# CSI2-KRIA-KV260_Rev01-2.net
KiCad netlist of a schematic drawn in Altium Designer
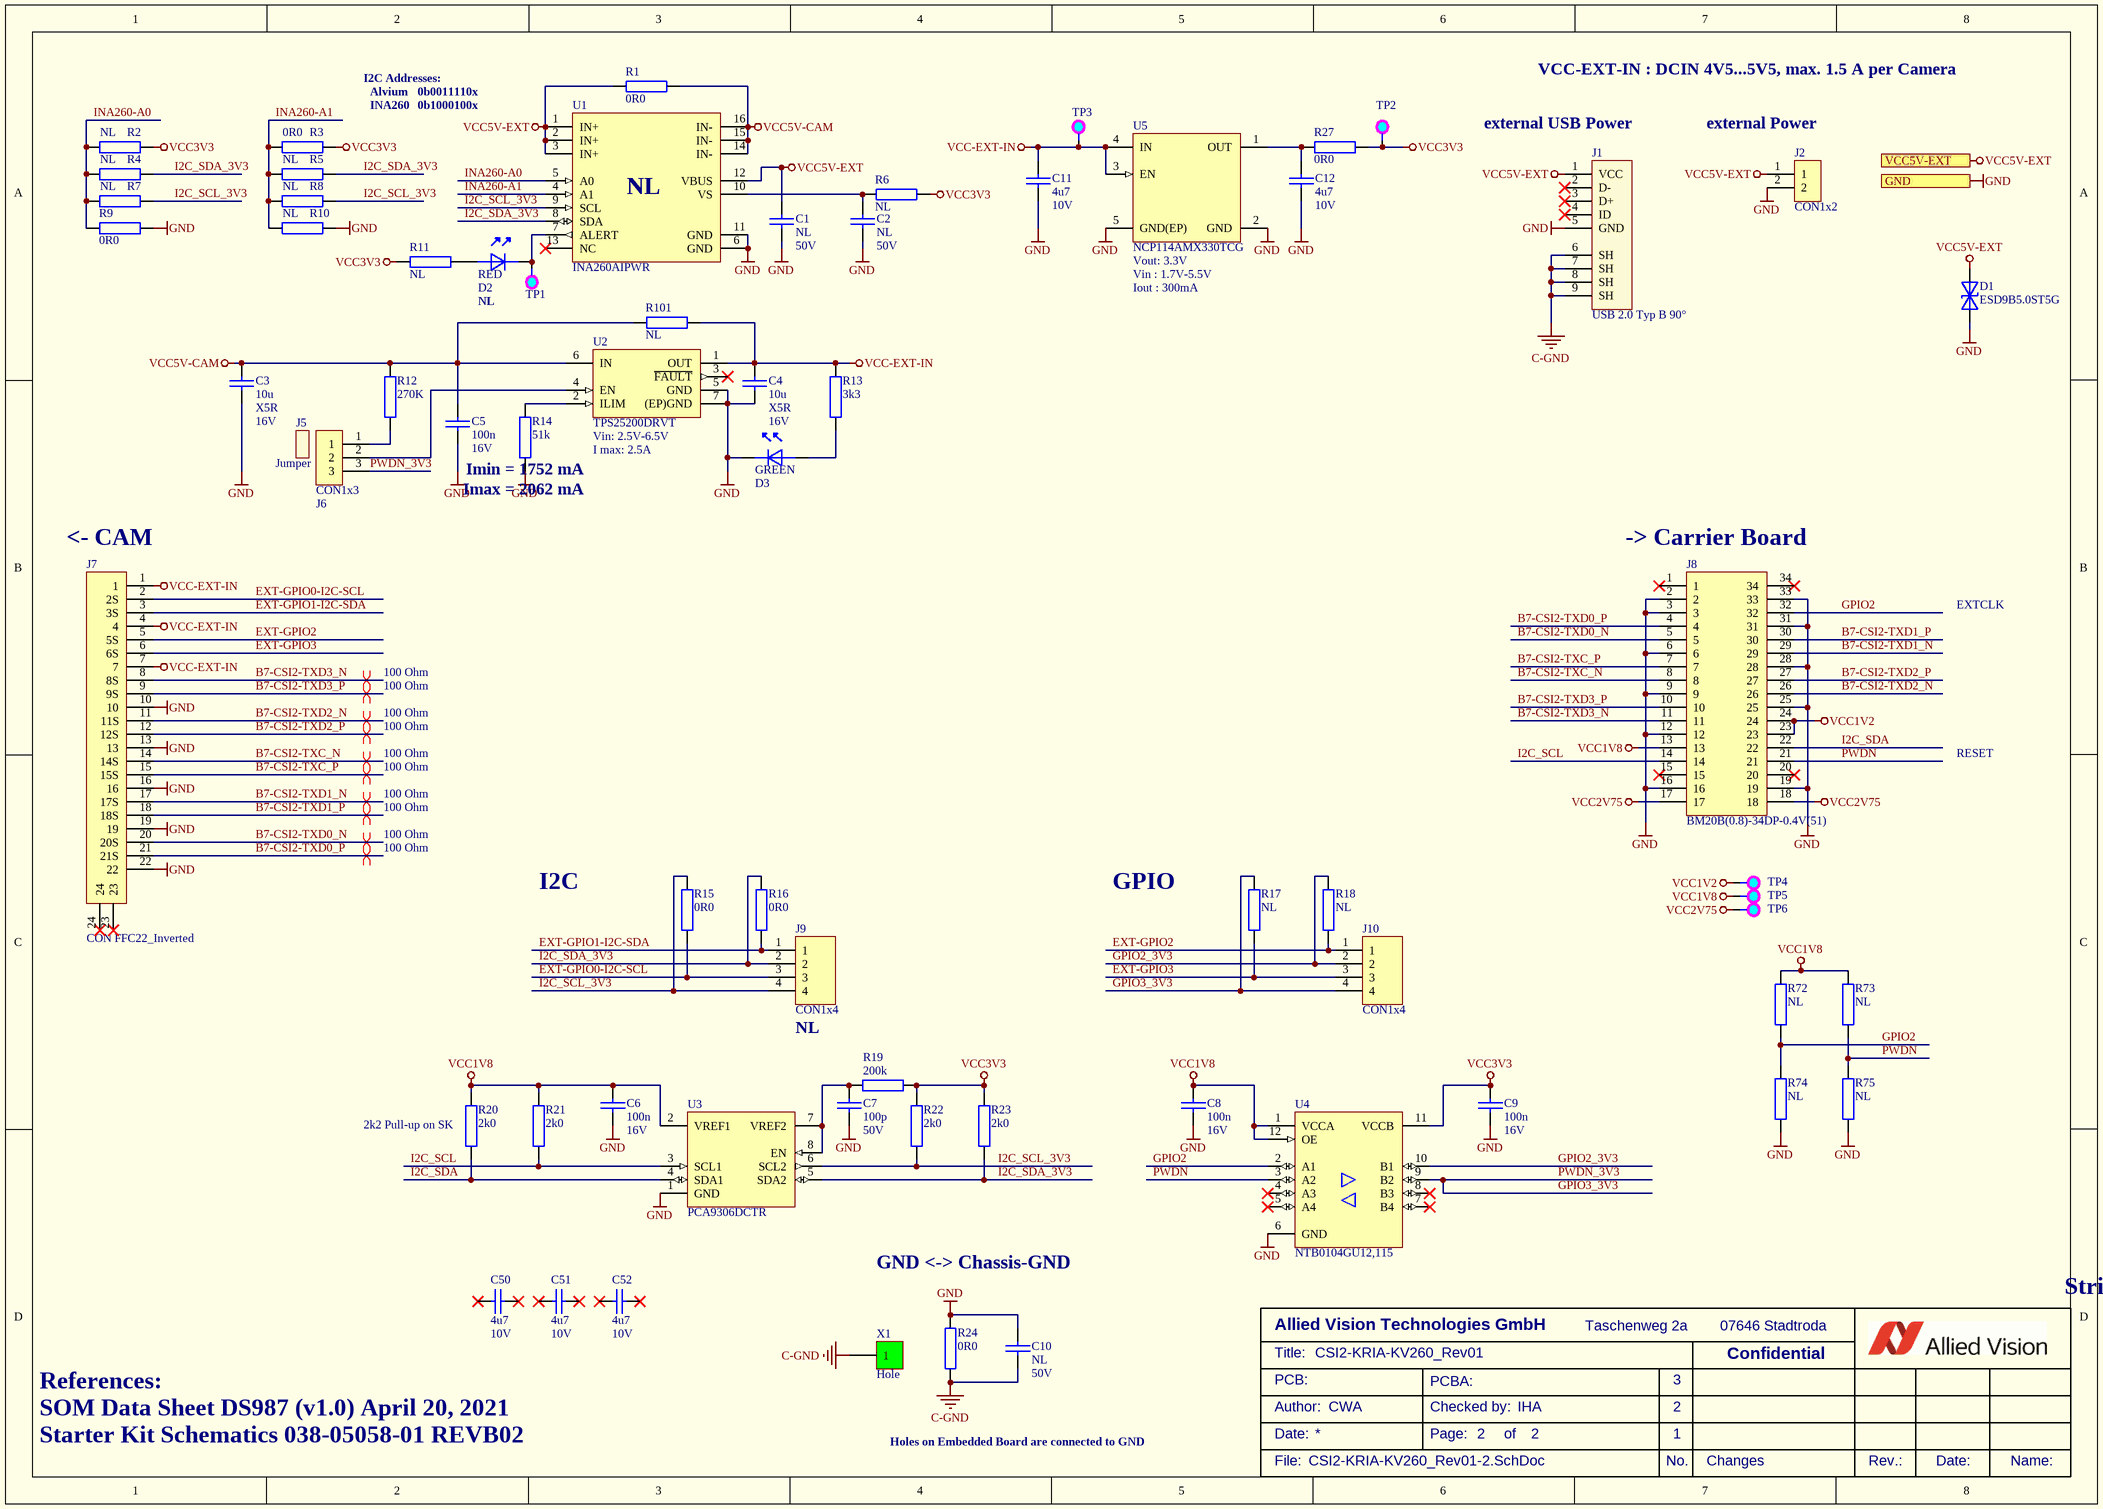
[diagram p0: CSI2-KRIA-KV260_Rev01-2.SchDoc]

(export (version "E")
  (design (tool "Eeschema 10.0.6"))
  (components
    (comp (ref "C1")
      (value "NL")
      (footprint "C-0402_0.55")
      (description "Capacitor Ceramic SMD/0402/50V/X7R/10%")
      (fields
        (field (name "MANUFACTURER") "several")
        (field (name "TOLERANCE") "10%")
        (field (name "VOLTAGE") "50V")
      )
      (libsource (lib "AVT_KHK_Lib") (part "C X 0402"))
    )
    (comp (ref "C2")
      (value "NL")
      (footprint "C-0402_0.55")
      (description "Capacitor Ceramic SMD/0402/50V/X7R/10%")
      (fields
        (field (name "MANUFACTURER") "several")
        (field (name "TOLERANCE") "10%")
        (field (name "VOLTAGE") "50V")
      )
      (libsource (lib "AVT_KHK_Lib") (part "C X 0402"))
    )
    (comp (ref "C3")
      (value "10u")
      (footprint "C-0805_1.4")
      (description "Capacitor Ceramic SMD/0805/16V/X5R/10%")
      (fields
        (field (name "KHK PART NUMBER") "K8340151")
        (field (name "MANUFACTURER") "several")
        (field (name "DIELECTRIC") "X5R")
        (field (name "VOLTAGE") "16V")
      )
      (libsource (lib "Passive") (part "C 10U 16V X5R 0805"))
    )
    (comp (ref "C4")
      (value "10u")
      (footprint "C-0805_1.4")
      (description "Capacitor Ceramic SMD/0805/16V/X5R/10%")
      (fields
        (field (name "KHK PART NUMBER") "K8340151")
        (field (name "MANUFACTURER") "several")
        (field (name "DIELECTRIC") "X5R")
        (field (name "VOLTAGE") "16V")
      )
      (libsource (lib "Passive") (part "C 10U 16V X5R 0805"))
    )
    (comp (ref "C5")
      (value "100n")
      (footprint "C-0402_0.55")
      (description "Capacitor Ceramic SMD/0402/16V/X7R/10%")
      (fields
        (field (name "KHK PART NUMBER") "K8340114")
        (field (name "MANUFACTURER") "several")
        (field (name "VOLTAGE") "16V")
      )
      (libsource (lib "Passive") (part "C 100N 10% 16V X7R 402"))
    )
    (comp (ref "C6")
      (value "100n")
      (footprint "C-0402_0.55")
      (description "Capacitor Ceramic SMD/0402/16V/X7R/10%")
      (fields
        (field (name "KHK PART NUMBER") "K8340114")
        (field (name "MANUFACTURER") "several")
        (field (name "VOLTAGE") "16V")
      )
      (libsource (lib "Passive") (part "C 100N 10% 16V X7R 402"))
    )
    (comp (ref "C7")
      (value "100p")
      (footprint "C-0402_0.55")
      (description "Capacitor Ceramic SMD/0402/50V/X7R/10%")
      (fields
        (field (name "KHK PART NUMBER") "K8340145")
        (field (name "MANUFACTURER") "several")
        (field (name "VOLTAGE") "50V")
      )
      (libsource (lib "Passive") (part "C 100P 50V X7R 0402"))
    )
    (comp (ref "C8")
      (value "100n")
      (footprint "C-0402_0.55")
      (description "Capacitor Ceramic SMD/0402/16V/X7R/10%")
      (fields
        (field (name "KHK PART NUMBER") "K8340114")
        (field (name "MANUFACTURER") "several")
        (field (name "VOLTAGE") "16V")
      )
      (libsource (lib "Passive") (part "C 100N 10% 16V X7R 402"))
    )
    (comp (ref "C9")
      (value "100n")
      (footprint "C-0402_0.55")
      (description "Capacitor Ceramic SMD/0402/16V/X7R/10%")
      (fields
        (field (name "KHK PART NUMBER") "K8340114")
        (field (name "MANUFACTURER") "several")
        (field (name "VOLTAGE") "16V")
      )
      (libsource (lib "Passive") (part "C 100N 10% 16V X7R 402"))
    )
    (comp (ref "C10")
      (value "NL")
      (footprint "C-0603_1.0")
      (description "Capacitor Ceramic SMD/0603/50V/X7R/10%")
      (fields
        (field (name "MANUFACTURER") "several")
        (field (name "TOLERANCE") "10%")
        (field (name "VOLTAGE") "50V")
      )
      (libsource (lib "AVT_KHK_Lib") (part "C X 0603"))
    )
    (comp (ref "C11")
      (value "4u7")
      (footprint "C-0603_1.0")
      (description "Capacitor Ceramic SMD/0603/10V/X5R/10%")
      (fields
        (field (name "KHK PART NUMBER") "1431")
        (field (name "MANUFACTURER") "several")
        (field (name "VOLTAGE") "10V")
      )
      (libsource (lib "Passive") (part "C 4U7 10V X5R 0603"))
    )
    (comp (ref "C12")
      (value "4u7")
      (footprint "C-0603_1.0")
      (description "Capacitor Ceramic SMD/0603/10V/X5R/10%")
      (fields
        (field (name "KHK PART NUMBER") "1431")
        (field (name "MANUFACTURER") "several")
        (field (name "VOLTAGE") "10V")
      )
      (libsource (lib "Passive") (part "C 4U7 10V X5R 0603"))
    )
    (comp (ref "C50")
      (value "4u7")
      (footprint "C-0603_1.0")
      (description "Capacitor Ceramic SMD/0603/10V/X5R/10%")
      (fields
        (field (name "KHK PART NUMBER") "1431")
        (field (name "MANUFACTURER") "several")
        (field (name "VOLTAGE") "10V")
      )
      (libsource (lib "Passive") (part "C 4U7 10V X5R 0603"))
    )
    (comp (ref "C51")
      (value "4u7")
      (footprint "C-0603_1.0")
      (description "Capacitor Ceramic SMD/0603/10V/X5R/10%")
      (fields
        (field (name "KHK PART NUMBER") "1431")
        (field (name "MANUFACTURER") "several")
        (field (name "VOLTAGE") "10V")
      )
      (libsource (lib "Passive") (part "C 4U7 10V X5R 0603"))
    )
    (comp (ref "C52")
      (value "4u7")
      (footprint "C-0603_1.0")
      (description "Capacitor Ceramic SMD/0603/10V/X5R/10%")
      (fields
        (field (name "KHK PART NUMBER") "1431")
        (field (name "MANUFACTURER") "several")
        (field (name "VOLTAGE") "10V")
      )
      (libsource (lib "Passive") (part "C 4U7 10V X5R 0603"))
    )
    (comp (ref "D1")
      (value "ESD9B5.0ST5G")
      (footprint "D-SOD923")
      (description "DIODE TVS; 400W; 5.8-7.8V; BIDIRECT")
      (fields (field (name "KHK PART NUMBER") "7250") (field (name "MANUFACTURER") "ON Semiconductor"))
      (libsource (lib "Bipolar") (part "D ESD9B5.0ST5G"))
    )
    (comp (ref "D2")
      (value "RED")
      (footprint "D-0603-LED")
      (description "Chip LED red 250mcd")
      (fields (field (name "KHK PART NUMBER") "8145") (field (name "MANUFACTURER") "Würth"))
      (libsource (lib "Bipolar") (part "D LED 0603 red"))
    )
    (comp (ref "D3")
      (value "GREEN")
      (footprint "D-0603-LED")
      (description "Chip LED green 430mcd")
      (fields (field (name "KHK PART NUMBER") "8172") (field (name "MANUFACTURER") "Würth"))
      (libsource (lib "Bipolar") (part "D LED 0603 green"))
    )
    (comp (ref "J1")
      (value "USB 2.0 Typ B 90°")
      (footprint "J-629105150521")
      (description "Micro USB 2.0 Typ B 90°")
      (fields (field (name "KHK PART NUMBER") "14360") (field (name "MANUFACTURER") "WE"))
      (libsource (lib "Connector") (part "CON USB 2.0 Typ B 90°"))
    )
    (comp (ref "J2")
      (value "CON1x2")
      (footprint "CON 1x2 RM2.54")
      (fields (field (name "MANUFACTURER") "several") (field (name "KHK PART NUMBER") "15337"))
      (libsource (lib "Connector") (part "CON 1x2 2.54 several"))
    )
    (comp (ref "J5")
      (value "Jumper")
      (footprint "J-JUMPER-2.54")
      (description "CON/JUMPER/STC02SYAN; 2-pin; 2.54mm; 3A; FEMALE; VERTICAL; BLACK")
      (fields (field (name "KHK PART NUMBER") "13444") (field (name "MANUFACTURER") "several"))
      (libsource (lib "Connector") (part "CON Jumper 2.54mm"))
    )
    (comp (ref "J6")
      (value "CON1x3")
      (footprint "CON 1x3 RM2.54")
      (fields (field (name "MANUFACTURER") "several") (field (name "KHK PART NUMBER") "15338"))
      (libsource (lib "Connector") (part "CON 1x3 2.54 several"))
    )
    (comp (ref "J7")
      (value "CON FFC22_Inverted")
      (footprint "J-FH55-22S-0.5SH - Inverted Pins")
      (description "FFC Connector 0.5mm shielded")
      (fields
        (field (name "KHK PART NUMBER") "10357")
        (field (name "MANUFACTURER PART NUMBER") "FH55-22S-0.5SH")
      )
      (libsource (lib "Connector") (part "CON FFC22_FH55-22S-0.5SH_Inverted"))
    )
    (comp (ref "J8")
      (value "BM20B(0.8)-34DP-0.4V(51)")
      (footprint "J-BM20B(0.8)-34DP")
      (description "CON/B2B/BM20B;34-pin;0.4;SMT;HEADER;VERTICAL")
      (fields (field (name "MANUFACTURER") "HiRose") (field (name "KHK PART NUMBER") "18690"))
      (libsource (lib "AVT_KHK_Lib") (part "CON BM20B(0.8)-34DP"))
    )
    (comp (ref "J9")
      (value "CON1x4")
      (footprint "CON 1x4 RM2.54")
      (fields (field (name "MANUFACTURER") "several") (field (name "KHK PART NUMBER") "15343"))
      (libsource (lib "Connector") (part "CON 1x4 2.54 several"))
    )
    (comp (ref "J10")
      (value "CON1x4")
      (footprint "CON 1x4 RM2.54")
      (fields (field (name "MANUFACTURER") "several") (field (name "KHK PART NUMBER") "15343"))
      (libsource (lib "Connector") (part "CON 1x4 2.54 several"))
    )
    (comp (ref "R1")
      (value "0R0")
      (footprint "R-0603_0.6")
      (description "Standard Resistor SMD/0603/1%/100mW/TK200")
      (fields (field (name "KHK PART NUMBER") "K8250041") (field (name "MANUFACTURER") "several"))
      (libsource (lib "AVT_KHK_Lib") (part "R 0R0 1% 0603"))
    )
    (comp (ref "R2")
      (value "NL")
      (footprint "R-0603_0.6")
      (description "Standard Resistor SMD/0603/1%/100mW/TK200")
      (fields (field (name "TOLERANCE") "1%"))
      (libsource (lib "AVT_KHK_Lib") (part "R X 0603"))
    )
    (comp (ref "R3")
      (value "0R0")
      (footprint "R-0603_0.6")
      (description "Standard Resistor SMD/0603/1%/100mW/TK200")
      (fields (field (name "KHK PART NUMBER") "K8250041") (field (name "MANUFACTURER") "several"))
      (libsource (lib "Passive") (part "R 0R0 1% 0603"))
    )
    (comp (ref "R4")
      (value "NL")
      (footprint "R-0603_0.6")
      (description "Standard Resistor SMD/0603/1%/100mW/TK200")
      (fields (field (name "TOLERANCE") "1%"))
      (libsource (lib "AVT_KHK_Lib") (part "R X 0603"))
    )
    (comp (ref "R5")
      (value "NL")
      (footprint "R-0603_0.6")
      (description "Standard Resistor SMD/0603/1%/100mW/TK200")
      (fields (field (name "TOLERANCE") "1%"))
      (libsource (lib "AVT_KHK_Lib") (part "R X 0603"))
    )
    (comp (ref "R6")
      (value "NL")
      (footprint "R-0603_0.6")
      (description "Standard Resistor SMD/0603/1%/100mW/TK200")
      (fields (field (name "TOLERANCE") "1%"))
      (libsource (lib "AVT_KHK_Lib") (part "R X 0603"))
    )
    (comp (ref "R7")
      (value "NL")
      (footprint "R-0603_0.6")
      (description "Standard Resistor SMD/0603/1%/100mW/TK200")
      (fields (field (name "TOLERANCE") "1%"))
      (libsource (lib "AVT_KHK_Lib") (part "R X 0603"))
    )
    (comp (ref "R8")
      (value "NL")
      (footprint "R-0603_0.6")
      (description "Standard Resistor SMD/0603/1%/100mW/TK200")
      (fields (field (name "TOLERANCE") "1%"))
      (libsource (lib "AVT_KHK_Lib") (part "R X 0603"))
    )
    (comp (ref "R9")
      (value "0R0")
      (footprint "R-0603_0.6")
      (description "Standard Resistor SMD/0603/1%/100mW/TK200")
      (fields (field (name "KHK PART NUMBER") "K8250041") (field (name "MANUFACTURER") "several"))
      (libsource (lib "Passive") (part "R 0R0 1% 0603"))
    )
    (comp (ref "R10")
      (value "NL")
      (footprint "R-0603_0.6")
      (description "Standard Resistor SMD/0603/1%/100mW/TK200")
      (fields (field (name "TOLERANCE") "1%"))
      (libsource (lib "AVT_KHK_Lib") (part "R X 0603"))
    )
    (comp (ref "R11")
      (value "NL")
      (footprint "R-0402_0.4")
      (description "Standard Resistor SMD/0402/1%/63mW/TK200")
      (fields (field (name "TOLERANCE") "1%"))
      (libsource (lib "AVT_KHK_Lib") (part "R X 0402"))
    )
    (comp (ref "R12")
      (value "270K")
      (footprint "R-0402_0.4")
      (description "Standard Resistor SMD/0402/1%/63mW/TK100")
      (fields (field (name "KHK PART NUMBER") "3875") (field (name "MANUFACTURER") "several"))
      (libsource (lib "Passive") (part "R 270K 1% 0402"))
    )
    (comp (ref "R13")
      (value "3k3")
      (footprint "R-0402_0.4")
      (description "Standard Resistor SMD/0402/1%/63mW/TK100")
      (fields (field (name "KHK PART NUMBER") "K8250347") (field (name "MANUFACTURER") "several"))
      (libsource (lib "Passive") (part "R 3k3 1% 0402"))
    )
    (comp (ref "R14")
      (value "51k")
      (footprint "R-0402_0.4")
      (description "Standard Resistor SMD/0402/1%/63mW/TK100")
      (fields (field (name "KHK PART NUMBER") "K8250273") (field (name "MANUFACTURER") "several"))
      (libsource (lib "Passive") (part "R 51K 1% 0402"))
    )
    (comp (ref "R15")
      (value "0R0")
      (footprint "R-0603_0.6")
      (description "Standard Resistor SMD/0603/1%/100mW/TK200")
      (fields (field (name "KHK PART NUMBER") "K8250041") (field (name "MANUFACTURER") "several"))
      (libsource (lib "Passive") (part "R 0R0 1% 0603"))
    )
    (comp (ref "R16")
      (value "0R0")
      (footprint "R-0603_0.6")
      (description "Standard Resistor SMD/0603/1%/100mW/TK200")
      (fields (field (name "KHK PART NUMBER") "K8250041") (field (name "MANUFACTURER") "several"))
      (libsource (lib "Passive") (part "R 0R0 1% 0603"))
    )
    (comp (ref "R17")
      (value "NL")
      (footprint "R-0603_0.6")
      (description "Standard Resistor SMD/0603/1%/100mW/TK200")
      (fields (field (name "TOLERANCE") "1%"))
      (libsource (lib "AVT_KHK_Lib") (part "R X 0603"))
    )
    (comp (ref "R18")
      (value "NL")
      (footprint "R-0603_0.6")
      (description "Standard Resistor SMD/0603/1%/100mW/TK200")
      (fields (field (name "TOLERANCE") "1%"))
      (libsource (lib "AVT_KHK_Lib") (part "R X 0603"))
    )
    (comp (ref "R19")
      (value "200k")
      (footprint "R-0402_0.4")
      (description "Standard Resistor SMD/0402/1%/63mW/TK100")
      (fields (field (name "KHK PART NUMBER") "K8250280") (field (name "MANUFACTURER") "several"))
      (libsource (lib "Passive") (part "R 200K 1% 0402"))
    )
    (comp (ref "R20")
      (value "2k0")
      (footprint "R-0402_0.4")
      (description "Standard Resistor SMD/0402/1%/63mW/TK100")
      (fields (field (name "KHK PART NUMBER") "K8250311") (field (name "MANUFACTURER") "several"))
      (libsource (lib "Passive") (part "R 2k0 1% 0402"))
    )
    (comp (ref "R21")
      (value "2k0")
      (footprint "R-0402_0.4")
      (description "Standard Resistor SMD/0402/1%/63mW/TK100")
      (fields (field (name "KHK PART NUMBER") "K8250311") (field (name "MANUFACTURER") "several"))
      (libsource (lib "Passive") (part "R 2k0 1% 0402"))
    )
    (comp (ref "R22")
      (value "2k0")
      (footprint "R-0402_0.4")
      (description "Standard Resistor SMD/0402/1%/63mW/TK100")
      (fields (field (name "KHK PART NUMBER") "K8250311") (field (name "MANUFACTURER") "several"))
      (libsource (lib "Passive") (part "R 2k0 1% 0402"))
    )
    (comp (ref "R23")
      (value "2k0")
      (footprint "R-0402_0.4")
      (description "Standard Resistor SMD/0402/1%/63mW/TK100")
      (fields (field (name "KHK PART NUMBER") "K8250311") (field (name "MANUFACTURER") "several"))
      (libsource (lib "Passive") (part "R 2k0 1% 0402"))
    )
    (comp (ref "R24")
      (value "0R0")
      (footprint "R-0603_0.6")
      (description "Standard Resistor SMD/0603/1%/100mW/TK200")
      (fields (field (name "KHK PART NUMBER") "K8250041") (field (name "MANUFACTURER") "several"))
      (libsource (lib "Passive") (part "R 0R0 1% 0603"))
    )
    (comp (ref "R27")
      (value "0R0")
      (footprint "R-0603_0.6")
      (description "Standard Resistor SMD/0603/1%/100mW/TK100")
      (fields (field (name "KHK PART NUMBER") "K8250041") (field (name "MANUFACTURER") "several"))
      (libsource (lib "Passive") (part "R 0R0 1% 0603"))
    )
    (comp (ref "R72")
      (value "NL")
      (footprint "R-0603_0.6")
      (description "Standard Resistor SMD/0603/1%/100mW/TK200")
      (fields (field (name "TOLERANCE") "1%"))
      (libsource (lib "AVT_KHK_Lib") (part "R X 0603"))
    )
    (comp (ref "R73")
      (value "NL")
      (footprint "R-0603_0.6")
      (description "Standard Resistor SMD/0603/1%/100mW/TK200")
      (fields (field (name "TOLERANCE") "1%"))
      (libsource (lib "AVT_KHK_Lib") (part "R X 0603"))
    )
    (comp (ref "R74")
      (value "NL")
      (footprint "R-0603_0.6")
      (description "Standard Resistor SMD/0603/1%/100mW/TK200")
      (fields (field (name "TOLERANCE") "1%"))
      (libsource (lib "AVT_KHK_Lib") (part "R X 0603"))
    )
    (comp (ref "R75")
      (value "NL")
      (footprint "R-0603_0.6")
      (description "Standard Resistor SMD/0603/1%/100mW/TK200")
      (fields (field (name "TOLERANCE") "1%"))
      (libsource (lib "AVT_KHK_Lib") (part "R X 0603"))
    )
    (comp (ref "R101")
      (value "NL")
      (footprint "R-0603_0.6")
      (description "Standard Resistor SMD/0603/1%/100mW/TK200")
      (fields (field (name "TOLERANCE") "1%"))
      (libsource (lib "AVT_KHK_Lib") (part "R X 0603"))
    )
    (comp (ref "TP1")
      (value "TP")
      (footprint "TP_16_10")
      (description "Testpoint: Pad=1,6mm; Hole=1,0mm")
      (libsource (lib "AVT_KHK_Lib") (part "TP_16_10"))
    )
    (comp (ref "TP2")
      (value "TP")
      (footprint "TP_16_10")
      (description "Testpoint: Pad=1,6mm; Hole=1,0mm")
      (libsource (lib "AVT_KHK_Lib") (part "TP_16_10"))
    )
    (comp (ref "TP3")
      (value "TP")
      (footprint "TP_16_10")
      (description "Testpoint: Pad=1,6mm; Hole=1,0mm")
      (libsource (lib "AVT_KHK_Lib") (part "TP_16_10"))
    )
    (comp (ref "TP4")
      (value "TP")
      (footprint "TP_16_10")
      (description "Testpoint: Pad=1,6mm; Hole=1,0mm")
      (libsource (lib "AVT_KHK_Lib") (part "TP_16_10"))
    )
    (comp (ref "TP5")
      (value "TP")
      (footprint "TP_16_10")
      (description "Testpoint: Pad=1,6mm; Hole=1,0mm")
      (libsource (lib "AVT_KHK_Lib") (part "TP_16_10"))
    )
    (comp (ref "TP6")
      (value "TP")
      (footprint "TP_16_10")
      (description "Testpoint: Pad=1,6mm; Hole=1,0mm")
      (libsource (lib "AVT_KHK_Lib") (part "TP_16_10"))
    )
    (comp (ref "U1")
      (value "INA260AIPWR")
      (footprint "IC-TSSOP16 6.4x5.1x1.2")
      (description "IC/PWR/CURR SHUNT MONITOR/2.7-5.5V;4.5mR/TSSOP16/5.0x4.4x1.2mm")
      (fields (field (name "KHK PART NUMBER") "16206") (field (name "MANUFACTURER") "TI"))
      (libsource (lib "Power") (part "IC INA260"))
    )
    (comp (ref "U2")
      (value "TPS25200DRVT")
      (footprint "IC-DFN06_2.0x2.0x0.8")
      (description "IC/PWR/LOADSW;2V5-6V5;2A5;0R099/6-WDFN/2x2x0.8mm")
      (fields
        (field (name "KHK PART NUMBER") "14277")
        (field (name "MANUFACTURER") "Texas Instruments")
        (field (name "VIN") "2.5V-6.5V")
        (field (name "I MAX") "2.5A")
      )
      (libsource (lib "Power") (part "IC  TPS25200DRVT"))
    )
    (comp (ref "U3")
      (value "PCA9306DCTR")
      (footprint "IC-TSSOP8_3.15x4.25x1.3")
      (description "IC/LOGIC/LEVELSHIFTER;I2C;AUTO-DIR;1V2-5V/SSOP-8/4.25x3.15x1.3mm")
      (fields (field (name "KHK PART NUMBER") "9555") (field (name "MANUFACTURER") "TI"))
      (libsource (lib "Logic") (part "IC PCA9306DCTR"))
    )
    (comp (ref "U4")
      (value "NTB0104GU12,115")
      (footprint "IC-XQFN12_1.7x2x0.5")
      (description "IC/LOGIC/Levelshifter;Auto-Dir;Bidirectional;Push-Pull;-40-+125°C/")
      (fields (field (name "MANUFACTURER") "NXP") (field (name "KHK PART NUMBER") "14383"))
      (libsource (lib "Logic") (part "IC NTB0104GU12,115"))
    )
    (comp (ref "U5")
      (value "NCP114AMX330TCG")
      (footprint "IC-XDFN4_1.0x1.0x0.6")
      (description "IC/PWR/LDO;1V7-5V5;3V3;0A3/XDFN4/1x1x0.6mm")
      (fields
        (field (name "KHK PART NUMBER") "20303")
        (field (name "MANUFACTURER") "ON Semi")
        (field (name "VOUT") "3.3V")
        (field (name "VIN") "Vin : 1.7V-5.5V")
        (field (name "IOUT") "Iout : 300mA")
      )
      (libsource (lib "AVT_KHK_Lib") (part "IC NCP114AMX330TCG"))
    )
    (comp (ref "X1")
      (value "Hole")
      (footprint "HOLE-3.4-6.0-DK")
      (description "HOLE 3.4-6-M3 Alternative")
      (libsource (lib "AVT_KHK_Lib") (part "PCB HOLE 3.4-6-DK"))
    )
  )
  (nets
    (net (code "1") (name "/B7-CSI2-TXC_N") (class "Default")
      (node (ref "J7") (pin "14") (pinfunction "14S_14") (pintype "passive"))
      (node (ref "J8") (pin "8") (pinfunction "8_8") (pintype "passive"))
    )
    (net (code "2") (name "/B7-CSI2-TXC_P") (class "Default")
      (node (ref "J7") (pin "15") (pinfunction "15S_15") (pintype "passive"))
      (node (ref "J8") (pin "7") (pinfunction "7_7") (pintype "passive"))
    )
    (net (code "3") (name "/B7-CSI2-TXD0_N") (class "Default")
      (node (ref "J7") (pin "20") (pinfunction "20S_20") (pintype "passive"))
      (node (ref "J8") (pin "5") (pinfunction "5_5") (pintype "passive"))
    )
    (net (code "4") (name "/B7-CSI2-TXD0_P") (class "Default")
      (node (ref "J7") (pin "21") (pinfunction "21S_21") (pintype "passive"))
      (node (ref "J8") (pin "4") (pinfunction "4_4") (pintype "passive"))
    )
    (net (code "5") (name "/B7-CSI2-TXD1_N") (class "Default")
      (node (ref "J7") (pin "17") (pinfunction "17S_17") (pintype "passive"))
      (node (ref "J8") (pin "29") (pinfunction "29_29") (pintype "passive"))
    )
    (net (code "6") (name "/B7-CSI2-TXD1_P") (class "Default")
      (node (ref "J7") (pin "18") (pinfunction "18S_18") (pintype "passive"))
      (node (ref "J8") (pin "30") (pinfunction "30_30") (pintype "passive"))
    )
    (net (code "7") (name "/B7-CSI2-TXD2_N") (class "Default")
      (node (ref "J7") (pin "11") (pinfunction "11S_11") (pintype "passive"))
      (node (ref "J8") (pin "26") (pinfunction "26_26") (pintype "passive"))
    )
    (net (code "8") (name "/B7-CSI2-TXD2_P") (class "Default")
      (node (ref "J7") (pin "12") (pinfunction "12S_12") (pintype "passive"))
      (node (ref "J8") (pin "27") (pinfunction "27_27") (pintype "passive"))
    )
    (net (code "9") (name "/B7-CSI2-TXD3_N") (class "Default")
      (node (ref "J7") (pin "8") (pinfunction "8S_8") (pintype "passive"))
      (node (ref "J8") (pin "11") (pinfunction "11_11") (pintype "passive"))
    )
    (net (code "10") (name "/B7-CSI2-TXD3_P") (class "Default")
      (node (ref "J7") (pin "9") (pinfunction "9S_9") (pintype "passive"))
      (node (ref "J8") (pin "10") (pinfunction "10_10") (pintype "passive"))
    )
    (net (code "11") (name "/EXT-GPIO0-I2C-SCL") (class "Default")
      (node (ref "J7") (pin "2") (pinfunction "2S_2") (pintype "passive"))
      (node (ref "J9") (pin "3") (pinfunction "3_3") (pintype "passive"))
      (node (ref "R15") (pin "1") (pinfunction "1_1") (pintype "passive"))
    )
    (net (code "12") (name "/EXT-GPIO1-I2C-SDA") (class "Default")
      (node (ref "J7") (pin "3") (pinfunction "3S_3") (pintype "passive"))
      (node (ref "J9") (pin "1") (pinfunction "1_1") (pintype "passive"))
      (node (ref "R16") (pin "1") (pinfunction "1_1") (pintype "passive"))
    )
    (net (code "13") (name "/EXT-GPIO2") (class "Default")
      (node (ref "J10") (pin "1") (pinfunction "1_1") (pintype "passive"))
      (node (ref "J7") (pin "5") (pinfunction "5S_5") (pintype "passive"))
      (node (ref "R18") (pin "1") (pinfunction "1_1") (pintype "passive"))
    )
    (net (code "14") (name "/EXT-GPIO3") (class "Default")
      (node (ref "J10") (pin "3") (pinfunction "3_3") (pintype "passive"))
      (node (ref "J7") (pin "6") (pinfunction "6S_6") (pintype "passive"))
      (node (ref "R17") (pin "1") (pinfunction "1_1") (pintype "passive"))
    )
    (net (code "15") (name "/GPIO2") (class "Default")
      (node (ref "J8") (pin "32") (pinfunction "32_32") (pintype "passive"))
      (node (ref "R72") (pin "1") (pinfunction "1_1") (pintype "passive"))
      (node (ref "R74") (pin "2") (pinfunction "2_2") (pintype "passive"))
      (node (ref "U4") (pin "2") (pinfunction "A1_2") (pintype "bidirectional"))
    )
    (net (code "16") (name "/GPIO2_3V3") (class "Default")
      (node (ref "J10") (pin "2") (pinfunction "2_2") (pintype "passive"))
      (node (ref "R18") (pin "2") (pinfunction "2_2") (pintype "passive"))
      (node (ref "U4") (pin "10") (pinfunction "B1_10") (pintype "bidirectional"))
    )
    (net (code "17") (name "/GPIO3_3V3") (class "Default")
      (node (ref "J10") (pin "4") (pinfunction "4_4") (pintype "passive"))
      (node (ref "J6") (pin "3") (pinfunction "3_3") (pintype "passive"))
      (node (ref "R17") (pin "2") (pinfunction "2_2") (pintype "passive"))
      (node (ref "U4") (pin "9") (pinfunction "B2_9") (pintype "bidirectional"))
    )
    (net (code "18") (name "/I2C_SCL") (class "Default")
      (node (ref "J8") (pin "14") (pinfunction "14_14") (pintype "passive"))
      (node (ref "R21") (pin "2") (pinfunction "2_2") (pintype "passive"))
      (node (ref "U3") (pin "3") (pinfunction "SCL1_3") (pintype "input"))
    )
    (net (code "19") (name "/I2C_SCL_3V3") (class "Default")
      (node (ref "J9") (pin "4") (pinfunction "4_4") (pintype "passive"))
      (node (ref "R15") (pin "2") (pinfunction "2_2") (pintype "passive"))
      (node (ref "R22") (pin "1") (pinfunction "1_1") (pintype "passive"))
      (node (ref "R7") (pin "1") (pinfunction "1_1") (pintype "passive"))
      (node (ref "R8") (pin "1") (pinfunction "1_1") (pintype "passive"))
      (node (ref "U1") (pin "9") (pinfunction "SCL_9") (pintype "input"))
      (node (ref "U3") (pin "6") (pinfunction "SCL2_6") (pintype "output"))
    )
    (net (code "20") (name "/I2C_SDA") (class "Default")
      (node (ref "J8") (pin "22") (pinfunction "22_22") (pintype "passive"))
      (node (ref "R20") (pin "2") (pinfunction "2_2") (pintype "passive"))
      (node (ref "U3") (pin "4") (pinfunction "SDA1_4") (pintype "bidirectional"))
    )
    (net (code "21") (name "/I2C_SDA_3V3") (class "Default")
      (node (ref "J9") (pin "2") (pinfunction "2_2") (pintype "passive"))
      (node (ref "R16") (pin "2") (pinfunction "2_2") (pintype "passive"))
      (node (ref "R23") (pin "1") (pinfunction "1_1") (pintype "passive"))
      (node (ref "R4") (pin "1") (pinfunction "1_1") (pintype "passive"))
      (node (ref "R5") (pin "1") (pinfunction "1_1") (pintype "passive"))
      (node (ref "U1") (pin "8") (pinfunction "SDA_8") (pintype "bidirectional"))
      (node (ref "U3") (pin "5") (pinfunction "SDA2_5") (pintype "bidirectional"))
    )
    (net (code "22") (name "/INA260-A0") (class "Default")
      (node (ref "R2") (pin "2") (pinfunction "2_2") (pintype "passive"))
      (node (ref "R4") (pin "2") (pinfunction "2_2") (pintype "passive"))
      (node (ref "R7") (pin "2") (pinfunction "2_2") (pintype "passive"))
      (node (ref "R9") (pin "2") (pinfunction "2_2") (pintype "passive"))
      (node (ref "U1") (pin "5") (pinfunction "A0_5") (pintype "input"))
    )
    (net (code "23") (name "/INA260-A1") (class "Default")
      (node (ref "R10") (pin "2") (pinfunction "2_2") (pintype "passive"))
      (node (ref "R3") (pin "2") (pinfunction "2_2") (pintype "passive"))
      (node (ref "R5") (pin "2") (pinfunction "2_2") (pintype "passive"))
      (node (ref "R8") (pin "2") (pinfunction "2_2") (pintype "passive"))
      (node (ref "U1") (pin "4") (pinfunction "A1_4") (pintype "input"))
    )
    (net (code "24") (name "/PWDN") (class "Default")
      (node (ref "J8") (pin "21") (pinfunction "21_21") (pintype "passive"))
      (node (ref "R73") (pin "1") (pinfunction "1_1") (pintype "passive"))
      (node (ref "R75") (pin "2") (pinfunction "2_2") (pintype "passive"))
      (node (ref "U4") (pin "3") (pinfunction "A2_3") (pintype "bidirectional"))
    )
    (net (code "25") (name "C-GND") (class "Default")
      (node (ref "C10") (pin "2") (pinfunction "2_2") (pintype "passive"))
      (node (ref "J1") (pin "6") (pinfunction "SH_6") (pintype "passive"))
      (node (ref "J1") (pin "7") (pinfunction "SH_7") (pintype "passive"))
      (node (ref "J1") (pin "8") (pinfunction "SH_8") (pintype "passive"))
      (node (ref "J1") (pin "9") (pinfunction "SH_9") (pintype "passive"))
      (node (ref "R24") (pin "1") (pinfunction "1_1") (pintype "passive"))
      (node (ref "X1") (pin "1") (pinfunction "1_1") (pintype "passive"))
    )
    (net (code "26") (name "GND") (class "Default")
      (node (ref "C1") (pin "2") (pinfunction "2_2") (pintype "passive"))
      (node (ref "C10") (pin "1") (pinfunction "1_1") (pintype "passive"))
      (node (ref "C11") (pin "2") (pinfunction "2_2") (pintype "passive"))
      (node (ref "C12") (pin "2") (pinfunction "2_2") (pintype "passive"))
      (node (ref "C2") (pin "2") (pinfunction "2_2") (pintype "passive"))
      (node (ref "C3") (pin "2") (pinfunction "2_2") (pintype "passive"))
      (node (ref "C4") (pin "2") (pinfunction "2_2") (pintype "passive"))
      (node (ref "C5") (pin "2") (pinfunction "2_2") (pintype "passive"))
      (node (ref "C6") (pin "2") (pinfunction "2_2") (pintype "passive"))
      (node (ref "C7") (pin "2") (pinfunction "2_2") (pintype "passive"))
      (node (ref "C8") (pin "2") (pinfunction "2_2") (pintype "passive"))
      (node (ref "C9") (pin "2") (pinfunction "2_2") (pintype "passive"))
      (node (ref "D1") (pin "A") (pinfunction "A_A") (pintype "passive"))
      (node (ref "D3") (pin "K") (pinfunction "2_K") (pintype "passive"))
      (node (ref "J1") (pin "5") (pinfunction "GND_5") (pintype "passive"))
      (node (ref "J2") (pin "2") (pinfunction "2_2") (pintype "passive"))
      (node (ref "J7") (pin "10") (pinfunction "10_10") (pintype "passive"))
      (node (ref "J7") (pin "13") (pinfunction "13_13") (pintype "passive"))
      (node (ref "J7") (pin "16") (pinfunction "16_16") (pintype "passive"))
      (node (ref "J7") (pin "19") (pinfunction "19_19") (pintype "passive"))
      (node (ref "J7") (pin "22") (pinfunction "22_22") (pintype "passive"))
      (node (ref "J8") (pin "12") (pinfunction "12_12") (pintype "passive"))
      (node (ref "J8") (pin "16") (pinfunction "16_16") (pintype "passive"))
      (node (ref "J8") (pin "19") (pinfunction "19_19") (pintype "passive"))
      (node (ref "J8") (pin "2") (pinfunction "2_2") (pintype "passive"))
      (node (ref "J8") (pin "25") (pinfunction "25_25") (pintype "passive"))
      (node (ref "J8") (pin "28") (pinfunction "28_28") (pintype "passive"))
      (node (ref "J8") (pin "3") (pinfunction "3_3") (pintype "passive"))
      (node (ref "J8") (pin "31") (pinfunction "31_31") (pintype "passive"))
      (node (ref "J8") (pin "33") (pinfunction "33_33") (pintype "passive"))
      (node (ref "J8") (pin "6") (pinfunction "6_6") (pintype "passive"))
      (node (ref "J8") (pin "9") (pinfunction "9_9") (pintype "passive"))
      (node (ref "R10") (pin "1") (pinfunction "1_1") (pintype "passive"))
      (node (ref "R14") (pin "1") (pinfunction "1_1") (pintype "passive"))
      (node (ref "R24") (pin "2") (pinfunction "2_2") (pintype "passive"))
      (node (ref "R74") (pin "1") (pinfunction "1_1") (pintype "passive"))
      (node (ref "R75") (pin "1") (pinfunction "1_1") (pintype "passive"))
      (node (ref "R9") (pin "1") (pinfunction "1_1") (pintype "passive"))
      (node (ref "U1") (pin "11") (pinfunction "GND_11") (pintype "power_in"))
      (node (ref "U1") (pin "6") (pinfunction "GND_6") (pintype "power_in"))
      (node (ref "U2") (pin "5") (pinfunction "GND_5") (pintype "power_in"))
      (node (ref "U2") (pin "7") (pinfunction "(EP)GND_7") (pintype "power_in"))
      (node (ref "U3") (pin "1") (pinfunction "GND_1") (pintype "power_in"))
      (node (ref "U4") (pin "6") (pinfunction "GND_6") (pintype "power_in"))
      (node (ref "U5") (pin "2") (pinfunction "GND_2") (pintype "power_in"))
      (node (ref "U5") (pin "5") (pinfunction "GND(EP)_5") (pintype "power_in"))
    )
    (net (code "27") (name "Net-(D2-1)") (class "Default")
      (node (ref "D2") (pin "A") (pinfunction "1_A") (pintype "passive"))
      (node (ref "R11") (pin "2") (pinfunction "2_2") (pintype "passive"))
    )
    (net (code "28") (name "Net-(D2-2)") (class "Default")
      (node (ref "D2") (pin "K") (pinfunction "2_K") (pintype "passive"))
      (node (ref "TP1") (pin "1") (pinfunction "1_1") (pintype "passive"))
      (node (ref "U1") (pin "7") (pinfunction "ALERT_7") (pintype "output"))
    )
    (net (code "29") (name "Net-(D3-1)") (class "Default")
      (node (ref "D3") (pin "A") (pinfunction "1_A") (pintype "passive"))
      (node (ref "R13") (pin "2") (pinfunction "2_2") (pintype "passive"))
    )
    (net (code "30") (name "Net-(J6-Pad1)") (class "Default")
      (node (ref "J6") (pin "1") (pinfunction "1_1") (pintype "passive"))
      (node (ref "R12") (pin "2") (pinfunction "2_2") (pintype "passive"))
    )
    (net (code "31") (name "Net-(U1-VS)") (class "Default")
      (node (ref "C2") (pin "1") (pinfunction "1_1") (pintype "passive"))
      (node (ref "R6") (pin "2") (pinfunction "2_2") (pintype "passive"))
      (node (ref "U1") (pin "10") (pinfunction "VS_10") (pintype "power_in"))
    )
    (net (code "32") (name "Net-(U2-EN)") (class "Default")
      (node (ref "J6") (pin "2") (pinfunction "2_2") (pintype "passive"))
      (node (ref "U2") (pin "4") (pinfunction "EN_4") (pintype "input"))
    )
    (net (code "33") (name "Net-(U2-ILIM)") (class "Default")
      (node (ref "R14") (pin "2") (pinfunction "2_2") (pintype "passive"))
      (node (ref "U2") (pin "2") (pinfunction "ILIM_2") (pintype "input"))
    )
    (net (code "34") (name "Net-(U3-EN)") (class "Default")
      (node (ref "C7") (pin "1") (pinfunction "1_1") (pintype "passive"))
      (node (ref "R19") (pin "1") (pinfunction "1_1") (pintype "passive"))
      (node (ref "U3") (pin "7") (pinfunction "VREF2_7") (pintype "power_in"))
      (node (ref "U3") (pin "8") (pinfunction "EN_8") (pintype "input"))
    )
    (net (code "35") (name "Net-(U5-OUT)") (class "Default")
      (node (ref "C12") (pin "1") (pinfunction "1_1") (pintype "passive"))
      (node (ref "R27") (pin "1") (pinfunction "1_1") (pintype "passive"))
      (node (ref "U5") (pin "1") (pinfunction "OUT_1") (pintype "power_in"))
    )
    (net (code "36") (name "VCC-EXT-IN") (class "Default")
      (node (ref "C11") (pin "1") (pinfunction "1_1") (pintype "passive"))
      (node (ref "C4") (pin "1") (pinfunction "1_1") (pintype "passive"))
      (node (ref "J7") (pin "1") (pinfunction "1_1") (pintype "passive"))
      (node (ref "J7") (pin "4") (pinfunction "4_4") (pintype "passive"))
      (node (ref "J7") (pin "7") (pinfunction "7_7") (pintype "passive"))
      (node (ref "R101") (pin "1") (pinfunction "1_1") (pintype "passive"))
      (node (ref "R13") (pin "1") (pinfunction "1_1") (pintype "passive"))
      (node (ref "TP3") (pin "1") (pinfunction "1_1") (pintype "passive"))
      (node (ref "U2") (pin "1") (pinfunction "OUT_1") (pintype "power_in"))
      (node (ref "U5") (pin "3") (pinfunction "EN_3") (pintype "input"))
      (node (ref "U5") (pin "4") (pinfunction "IN_4") (pintype "power_in"))
    )
    (net (code "37") (name "VCC1V2") (class "Default")
      (node (ref "J8") (pin "23") (pinfunction "23_23") (pintype "passive"))
      (node (ref "J8") (pin "24") (pinfunction "24_24") (pintype "passive"))
      (node (ref "TP4") (pin "1") (pinfunction "1_1") (pintype "passive"))
    )
    (net (code "38") (name "VCC1V8") (class "Default")
      (node (ref "C6") (pin "1") (pinfunction "1_1") (pintype "passive"))
      (node (ref "C8") (pin "1") (pinfunction "1_1") (pintype "passive"))
      (node (ref "J8") (pin "13") (pinfunction "13_13") (pintype "passive"))
      (node (ref "R20") (pin "1") (pinfunction "1_1") (pintype "passive"))
      (node (ref "R21") (pin "1") (pinfunction "1_1") (pintype "passive"))
      (node (ref "R72") (pin "2") (pinfunction "2_2") (pintype "passive"))
      (node (ref "R73") (pin "2") (pinfunction "2_2") (pintype "passive"))
      (node (ref "TP5") (pin "1") (pinfunction "1_1") (pintype "passive"))
      (node (ref "U3") (pin "2") (pinfunction "VREF1_2") (pintype "power_in"))
      (node (ref "U4") (pin "1") (pinfunction "VCCA_1") (pintype "power_in"))
      (node (ref "U4") (pin "12") (pinfunction "OE_12") (pintype "input"))
    )
    (net (code "39") (name "VCC2V75") (class "Default")
      (node (ref "J8") (pin "17") (pinfunction "17_17") (pintype "passive"))
      (node (ref "J8") (pin "18") (pinfunction "18_18") (pintype "passive"))
      (node (ref "TP6") (pin "1") (pinfunction "1_1") (pintype "passive"))
    )
    (net (code "40") (name "VCC3V3") (class "Default")
      (node (ref "C9") (pin "1") (pinfunction "1_1") (pintype "passive"))
      (node (ref "R11") (pin "1") (pinfunction "1_1") (pintype "passive"))
      (node (ref "R19") (pin "2") (pinfunction "2_2") (pintype "passive"))
      (node (ref "R2") (pin "1") (pinfunction "1_1") (pintype "passive"))
      (node (ref "R22") (pin "2") (pinfunction "2_2") (pintype "passive"))
      (node (ref "R23") (pin "2") (pinfunction "2_2") (pintype "passive"))
      (node (ref "R27") (pin "2") (pinfunction "2_2") (pintype "passive"))
      (node (ref "R3") (pin "1") (pinfunction "1_1") (pintype "passive"))
      (node (ref "R6") (pin "1") (pinfunction "1_1") (pintype "passive"))
      (node (ref "TP2") (pin "1") (pinfunction "1_1") (pintype "passive"))
      (node (ref "U4") (pin "11") (pinfunction "VCCB_11") (pintype "power_in"))
    )
    (net (code "41") (name "VCC5V-CAM") (class "Default")
      (node (ref "C3") (pin "1") (pinfunction "1_1") (pintype "passive"))
      (node (ref "C5") (pin "1") (pinfunction "1_1") (pintype "passive"))
      (node (ref "R1") (pin "1") (pinfunction "1_1") (pintype "passive"))
      (node (ref "R101") (pin "2") (pinfunction "2_2") (pintype "passive"))
      (node (ref "R12") (pin "1") (pinfunction "1_1") (pintype "passive"))
      (node (ref "U1") (pin "14") (pinfunction "IN-_14") (pintype "passive"))
      (node (ref "U1") (pin "15") (pinfunction "IN-_15") (pintype "passive"))
      (node (ref "U1") (pin "16") (pinfunction "IN-_16") (pintype "passive"))
      (node (ref "U2") (pin "6") (pinfunction "IN_6") (pintype "power_in"))
    )
    (net (code "42") (name "VCC5V-EXT") (class "Default")
      (node (ref "C1") (pin "1") (pinfunction "1_1") (pintype "passive"))
      (node (ref "D1") (pin "K") (pinfunction "K_K") (pintype "passive"))
      (node (ref "J1") (pin "1") (pinfunction "VCC_1") (pintype "passive"))
      (node (ref "J2") (pin "1") (pinfunction "1_1") (pintype "passive"))
      (node (ref "R1") (pin "2") (pinfunction "2_2") (pintype "passive"))
      (node (ref "U1") (pin "1") (pinfunction "IN+_1") (pintype "passive"))
      (node (ref "U1") (pin "12") (pinfunction "VBUS_12") (pintype "power_in"))
      (node (ref "U1") (pin "2") (pinfunction "IN+_2") (pintype "passive"))
      (node (ref "U1") (pin "3") (pinfunction "IN+_3") (pintype "passive"))
    )
    (net (code "43") (name "unconnected-(C50-Pad1)") (class "Default")
      (node (ref "C50") (pin "1") (pinfunction "1_1") (pintype "passive+no_connect"))
    )
    (net (code "44") (name "unconnected-(C50-Pad2)") (class "Default")
      (node (ref "C50") (pin "2") (pinfunction "2_2") (pintype "passive+no_connect"))
    )
    (net (code "45") (name "unconnected-(C51-Pad1)") (class "Default")
      (node (ref "C51") (pin "1") (pinfunction "1_1") (pintype "passive+no_connect"))
    )
    (net (code "46") (name "unconnected-(C51-Pad2)") (class "Default")
      (node (ref "C51") (pin "2") (pinfunction "2_2") (pintype "passive+no_connect"))
    )
    (net (code "47") (name "unconnected-(C52-Pad1)") (class "Default")
      (node (ref "C52") (pin "1") (pinfunction "1_1") (pintype "passive+no_connect"))
    )
    (net (code "48") (name "unconnected-(C52-Pad2)") (class "Default")
      (node (ref "C52") (pin "2") (pinfunction "2_2") (pintype "passive+no_connect"))
    )
    (net (code "49") (name "unconnected-(J1-D+-Pad3)") (class "Default")
      (node (ref "J1") (pin "3") (pinfunction "D+_3") (pintype "passive+no_connect"))
    )
    (net (code "50") (name "unconnected-(J1-D--Pad2)") (class "Default")
      (node (ref "J1") (pin "2") (pinfunction "D-_2") (pintype "passive+no_connect"))
    )
    (net (code "51") (name "unconnected-(J1-ID-Pad4)") (class "Default")
      (node (ref "J1") (pin "4") (pinfunction "ID_4") (pintype "passive+no_connect"))
    )
    (net (code "52") (name "unconnected-(J7-Pad23)") (class "Default")
      (node (ref "J7") (pin "23") (pinfunction "23_23") (pintype "passive+no_connect"))
    )
    (net (code "53") (name "unconnected-(J7-Pad24)") (class "Default")
      (node (ref "J7") (pin "24") (pinfunction "24_24") (pintype "passive+no_connect"))
    )
    (net (code "54") (name "unconnected-(J8-Pad1)") (class "Default")
      (node (ref "J8") (pin "1") (pinfunction "1_1") (pintype "passive+no_connect"))
    )
    (net (code "55") (name "unconnected-(J8-Pad15)") (class "Default")
      (node (ref "J8") (pin "15") (pinfunction "15_15") (pintype "passive+no_connect"))
    )
    (net (code "56") (name "unconnected-(J8-Pad20)") (class "Default")
      (node (ref "J8") (pin "20") (pinfunction "20_20") (pintype "passive+no_connect"))
    )
    (net (code "57") (name "unconnected-(J8-Pad34)") (class "Default")
      (node (ref "J8") (pin "34") (pinfunction "34_34") (pintype "passive+no_connect"))
    )
    (net (code "58") (name "unconnected-(U1-NC-Pad13)") (class "Default")
      (node (ref "U1") (pin "13") (pinfunction "NC_13") (pintype "passive+no_connect"))
    )
    (net (code "59") (name "unconnected-(U2-~{FAULT}-Pad3)") (class "Default")
      (node (ref "U2") (pin "3") (pinfunction "~{FAULT}_3") (pintype "output+no_connect"))
    )
    (net (code "60") (name "unconnected-(U4-A3-Pad4)") (class "Default")
      (node (ref "U4") (pin "4") (pinfunction "A3_4") (pintype "bidirectional+no_connect"))
    )
    (net (code "61") (name "unconnected-(U4-A4-Pad5)") (class "Default")
      (node (ref "U4") (pin "5") (pinfunction "A4_5") (pintype "bidirectional+no_connect"))
    )
    (net (code "62") (name "unconnected-(U4-B3-Pad8)") (class "Default")
      (node (ref "U4") (pin "8") (pinfunction "B3_8") (pintype "bidirectional+no_connect"))
    )
    (net (code "63") (name "unconnected-(U4-B4-Pad7)") (class "Default")
      (node (ref "U4") (pin "7") (pinfunction "B4_7") (pintype "bidirectional+no_connect"))
    )
  )
)
